# Sheet1.net
KiCad netlist of a schematic drawn in Altium Designer
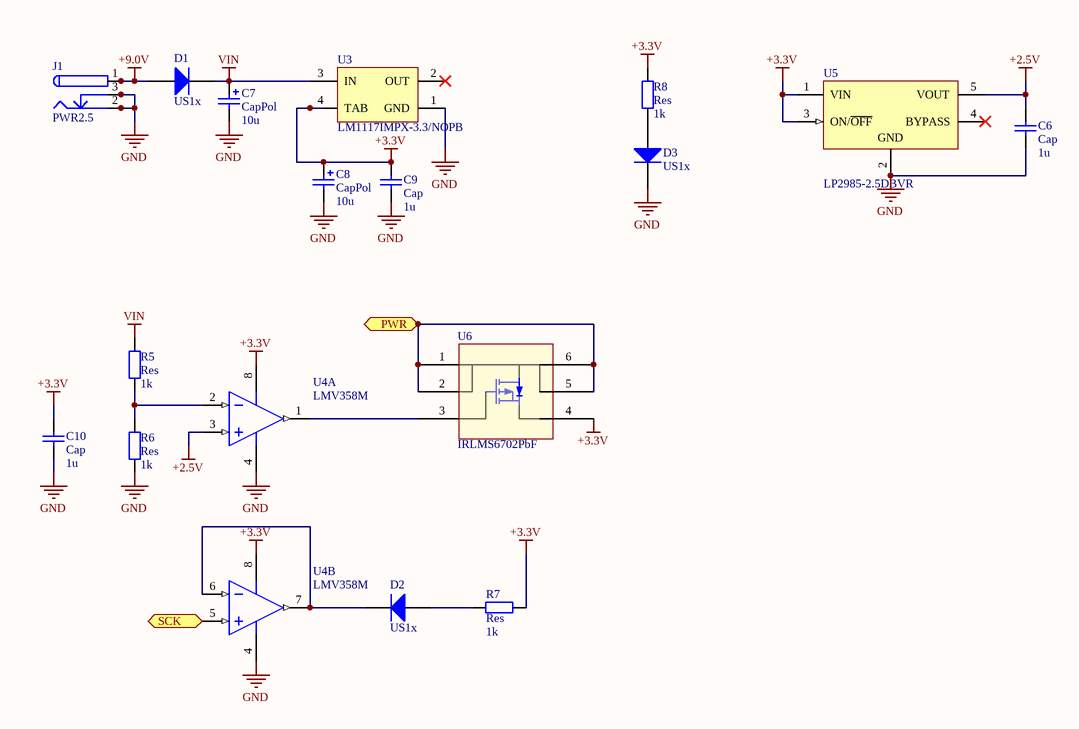
[diagram p0: Sheet1.SchDoc]

(export (version "E")
  (design (tool "Eeschema 10.0.6"))
  (components
    (comp (ref "C6")
      (value "Cap")
      (footprint "Capacitors:0805")
      (fields (field (name "ALTIUM_VALUE") "1u"))
      (libsource (lib "Capacitors") (part "Cap"))
    )
    (comp (ref "C7")
      (value "CapPol")
      (footprint "Capacitors:CASE C")
      (description "Polarized Capacitor (Radial)")
      (fields (field (name "ALTIUM_VALUE") "10u"))
      (libsource (lib "Capacitors") (part "CapPol"))
    )
    (comp (ref "C8")
      (value "CapPol")
      (footprint "Capacitors:CASE C")
      (description "Polarized Capacitor (Radial)")
      (fields (field (name "ALTIUM_VALUE") "10u"))
      (libsource (lib "Capacitors") (part "CapPol"))
    )
    (comp (ref "C9")
      (value "Cap")
      (footprint "Capacitors:0805")
      (fields (field (name "ALTIUM_VALUE") "1u"))
      (libsource (lib "Capacitors") (part "Cap"))
    )
    (comp (ref "C10")
      (value "Cap")
      (footprint "Capacitors:0805")
      (fields (field (name "ALTIUM_VALUE") "1u"))
      (libsource (lib "Capacitors") (part "Cap"))
    )
    (comp (ref "D1")
      (value "US1x")
      (footprint "Vishay Intertechnology:D0-214AC (SMA)")
      (description "Ultrafast Rectifier")
      (libsource (lib "Vishay Intertechnology") (part "US1x"))
    )
    (comp (ref "D2")
      (value "US1x")
      (footprint "Vishay Intertechnology:D0-214AC (SMA)")
      (description "Ultrafast Rectifier")
      (libsource (lib "Vishay Intertechnology") (part "US1x"))
    )
    (comp (ref "D3")
      (value "US1x")
      (footprint "Vishay Intertechnology:D0-214AC (SMA)")
      (description "Ultrafast Rectifier")
      (libsource (lib "Vishay Intertechnology") (part "US1x"))
    )
    (comp (ref "J1")
      (value "PWR2.5")
      (footprint "Connectors:KLD-0202")
      (description "Low Voltage Power Supply Connector")
      (libsource (lib "Connectors") (part "PWR2.5"))
    )
    (comp (ref "R5")
      (value "Res")
      (footprint "Resistors:0805")
      (fields (field (name "ALTIUM_VALUE") "1k"))
      (libsource (lib "") (part "Res_1"))
    )
    (comp (ref "R6")
      (value "Res")
      (footprint "Resistors:0805")
      (fields (field (name "ALTIUM_VALUE") "1k"))
      (libsource (lib "") (part "Res_1"))
    )
    (comp (ref "R7")
      (value "Res")
      (footprint "Resistors:0805")
      (fields (field (name "ALTIUM_VALUE") "1k"))
      (libsource (lib "Resistors") (part "Res"))
    )
    (comp (ref "R8")
      (value "Res")
      (footprint "Resistors:0805")
      (fields (field (name "ALTIUM_VALUE") "1k"))
      (libsource (lib "") (part "Res_2"))
    )
    (comp (ref "U3")
      (value "LM1117IMPX-3.3/NOPB")
      (footprint "MP04A_N")
      (description "800mA Low-Dropout Linear Regulator, 4-pin SOT-223, Pb-Free")
      (fields (field (name "MANUFACTURER") "National Semiconductor"))
      (libsource (lib "National Semiconductor LDO") (part "LM1117IMPX-3.3/NOPB"))
    )
    (comp (ref "U4")
      (value "LMV358M")
      (footprint "M08A_N")
      (description "General Purpose, Low Voltage, Rail-to-Rail Output Operational Amplifiers, 8-pin Narrow SOIC")
      (fields (field (name "MANUFACTURER") "National Semiconductor"))
      (libsource (lib "National Semiconductor Amplifier") (part "LMV358M"))
    )
    (comp (ref "U5")
      (value "LP2985-2.5DBVR")
      (footprint "TI-DBV5_N")
      (fields (field (name "MANUFACTURER") "Texas Instruments") (field (name "PARTNUMBER") "LP2985-10DBVR"))
      (libsource (lib "TI Power Management Linear Regulator Single Channel LDO (0-350mA)") (part "LP2985-10DBVR"))
    )
    (comp (ref "U6")
      (value "IRLMS6702PbF")
      (footprint "International Rectifier:SuperSOT-6")
      (libsource (lib "International Rectifier") (part "IRLMS6702PbF"))
    )
  )
  (nets
    (net (code "1") (name "+2.5V") (class "Default")
      (node (ref "C6") (pin "2") (pinfunction "2_2") (pintype "passive"))
      (node (ref "U4") (pin "3") (pinfunction "INA+_3") (pintype "input"))
      (node (ref "U5") (pin "5") (pinfunction "VOUT_5") (pintype "power_in"))
    )
    (net (code "2") (name "+3.3V") (class "Default")
      (node (ref "C10") (pin "2") (pinfunction "2_2") (pintype "passive"))
      (node (ref "C8") (pin "1") (pinfunction "1_1") (pintype "passive"))
      (node (ref "C9") (pin "2") (pinfunction "2_2") (pintype "passive"))
      (node (ref "R7") (pin "1") (pinfunction "1_1") (pintype "passive"))
      (node (ref "R8") (pin "1") (pinfunction "1_1") (pintype "passive"))
      (node (ref "U3") (pin "4") (pinfunction "TAB_4") (pintype "power_in"))
      (node (ref "U4") (pin "8") (pinfunction "V+_8") (pintype "power_in"))
      (node (ref "U5") (pin "1") (pinfunction "VIN_1") (pintype "power_in"))
      (node (ref "U5") (pin "3") (pinfunction "ON/~{OFF}_3") (pintype "input"))
      (node (ref "U6") (pin "4") (pinfunction "S_4") (pintype "passive"))
    )
    (net (code "3") (name "+9.0V") (class "Default")
      (node (ref "D1") (pin "1") (pinfunction "A_1") (pintype "passive"))
      (node (ref "J1") (pin "1") (pinfunction "1_1") (pintype "power_in"))
      (node (ref "J1") (pin "1A") (pinfunction "1A_1A") (pintype "power_in"))
    )
    (net (code "4") (name "/PWR") (class "Default")
      (node (ref "U6") (pin "1") (pinfunction "D_1") (pintype "passive"))
      (node (ref "U6") (pin "2") (pinfunction "D_2") (pintype "passive"))
      (node (ref "U6") (pin "5") (pinfunction "D_5") (pintype "passive"))
      (node (ref "U6") (pin "6") (pinfunction "D_6") (pintype "passive"))
    )
    (net (code "5") (name "/SCK") (class "Default")
      (node (ref "U4") (pin "5") (pinfunction "INB+_5") (pintype "input"))
    )
    (net (code "6") (name "GND") (class "Default")
      (node (ref "C10") (pin "1") (pinfunction "1_1") (pintype "passive"))
      (node (ref "C6") (pin "1") (pinfunction "1_1") (pintype "passive"))
      (node (ref "C7") (pin "2") (pinfunction "2_2") (pintype "passive"))
      (node (ref "C8") (pin "2") (pinfunction "2_2") (pintype "passive"))
      (node (ref "C9") (pin "1") (pinfunction "1_1") (pintype "passive"))
      (node (ref "D3") (pin "2") (pinfunction "K_2") (pintype "passive"))
      (node (ref "J1") (pin "2") (pinfunction "2_2") (pintype "power_in"))
      (node (ref "J1") (pin "2A") (pinfunction "2A_2A") (pintype "power_in"))
      (node (ref "J1") (pin "3") (pinfunction "3_3") (pintype "power_in"))
      (node (ref "J1") (pin "3A") (pinfunction "3A_3A") (pintype "power_in"))
      (node (ref "R6") (pin "1") (pinfunction "1_1") (pintype "passive"))
      (node (ref "U3") (pin "1") (pinfunction "GND_1") (pintype "power_in"))
      (node (ref "U4") (pin "4") (pinfunction "V-_4") (pintype "power_in"))
      (node (ref "U5") (pin "2") (pinfunction "GND_2") (pintype "power_in"))
    )
    (net (code "7") (name "Net-(D2-A)") (class "Default")
      (node (ref "D2") (pin "1") (pinfunction "A_1") (pintype "passive"))
      (node (ref "R7") (pin "2") (pinfunction "2_2") (pintype "passive"))
    )
    (net (code "8") (name "Net-(D2-K)") (class "Default")
      (node (ref "D2") (pin "2") (pinfunction "K_2") (pintype "passive"))
      (node (ref "U4") (pin "6") (pinfunction "INB-_6") (pintype "input"))
      (node (ref "U4") (pin "7") (pinfunction "OUTB_7") (pintype "output"))
    )
    (net (code "9") (name "Net-(D3-A)") (class "Default")
      (node (ref "D3") (pin "1") (pinfunction "A_1") (pintype "passive"))
      (node (ref "R8") (pin "2") (pinfunction "2_2") (pintype "passive"))
    )
    (net (code "10") (name "Net-(U4A-INA-)") (class "Default")
      (node (ref "R5") (pin "1") (pinfunction "1_1") (pintype "passive"))
      (node (ref "R6") (pin "2") (pinfunction "2_2") (pintype "passive"))
      (node (ref "U4") (pin "2") (pinfunction "INA-_2") (pintype "input"))
    )
    (net (code "11") (name "Net-(U4A-OUTA)") (class "Default")
      (node (ref "U4") (pin "1") (pinfunction "OUTA_1") (pintype "output"))
      (node (ref "U6") (pin "3") (pinfunction "G_3") (pintype "passive"))
    )
    (net (code "12") (name "VIN") (class "Default")
      (node (ref "C7") (pin "1") (pinfunction "1_1") (pintype "passive"))
      (node (ref "D1") (pin "2") (pinfunction "K_2") (pintype "passive"))
      (node (ref "R5") (pin "2") (pinfunction "2_2") (pintype "passive"))
      (node (ref "U3") (pin "3") (pinfunction "IN_3") (pintype "power_in"))
    )
    (net (code "13") (name "unconnected-(U3-OUT-Pad2)") (class "Default")
      (node (ref "U3") (pin "2") (pinfunction "OUT_2") (pintype "power_in+no_connect"))
    )
    (net (code "14") (name "unconnected-(U5-BYPASS-Pad4)") (class "Default")
      (node (ref "U5") (pin "4") (pinfunction "BYPASS_4") (pintype "passive+no_connect"))
    )
  )
)
